# zigduino-micro-2.net
KiCad netlist of a schematic drawn in EAGLE
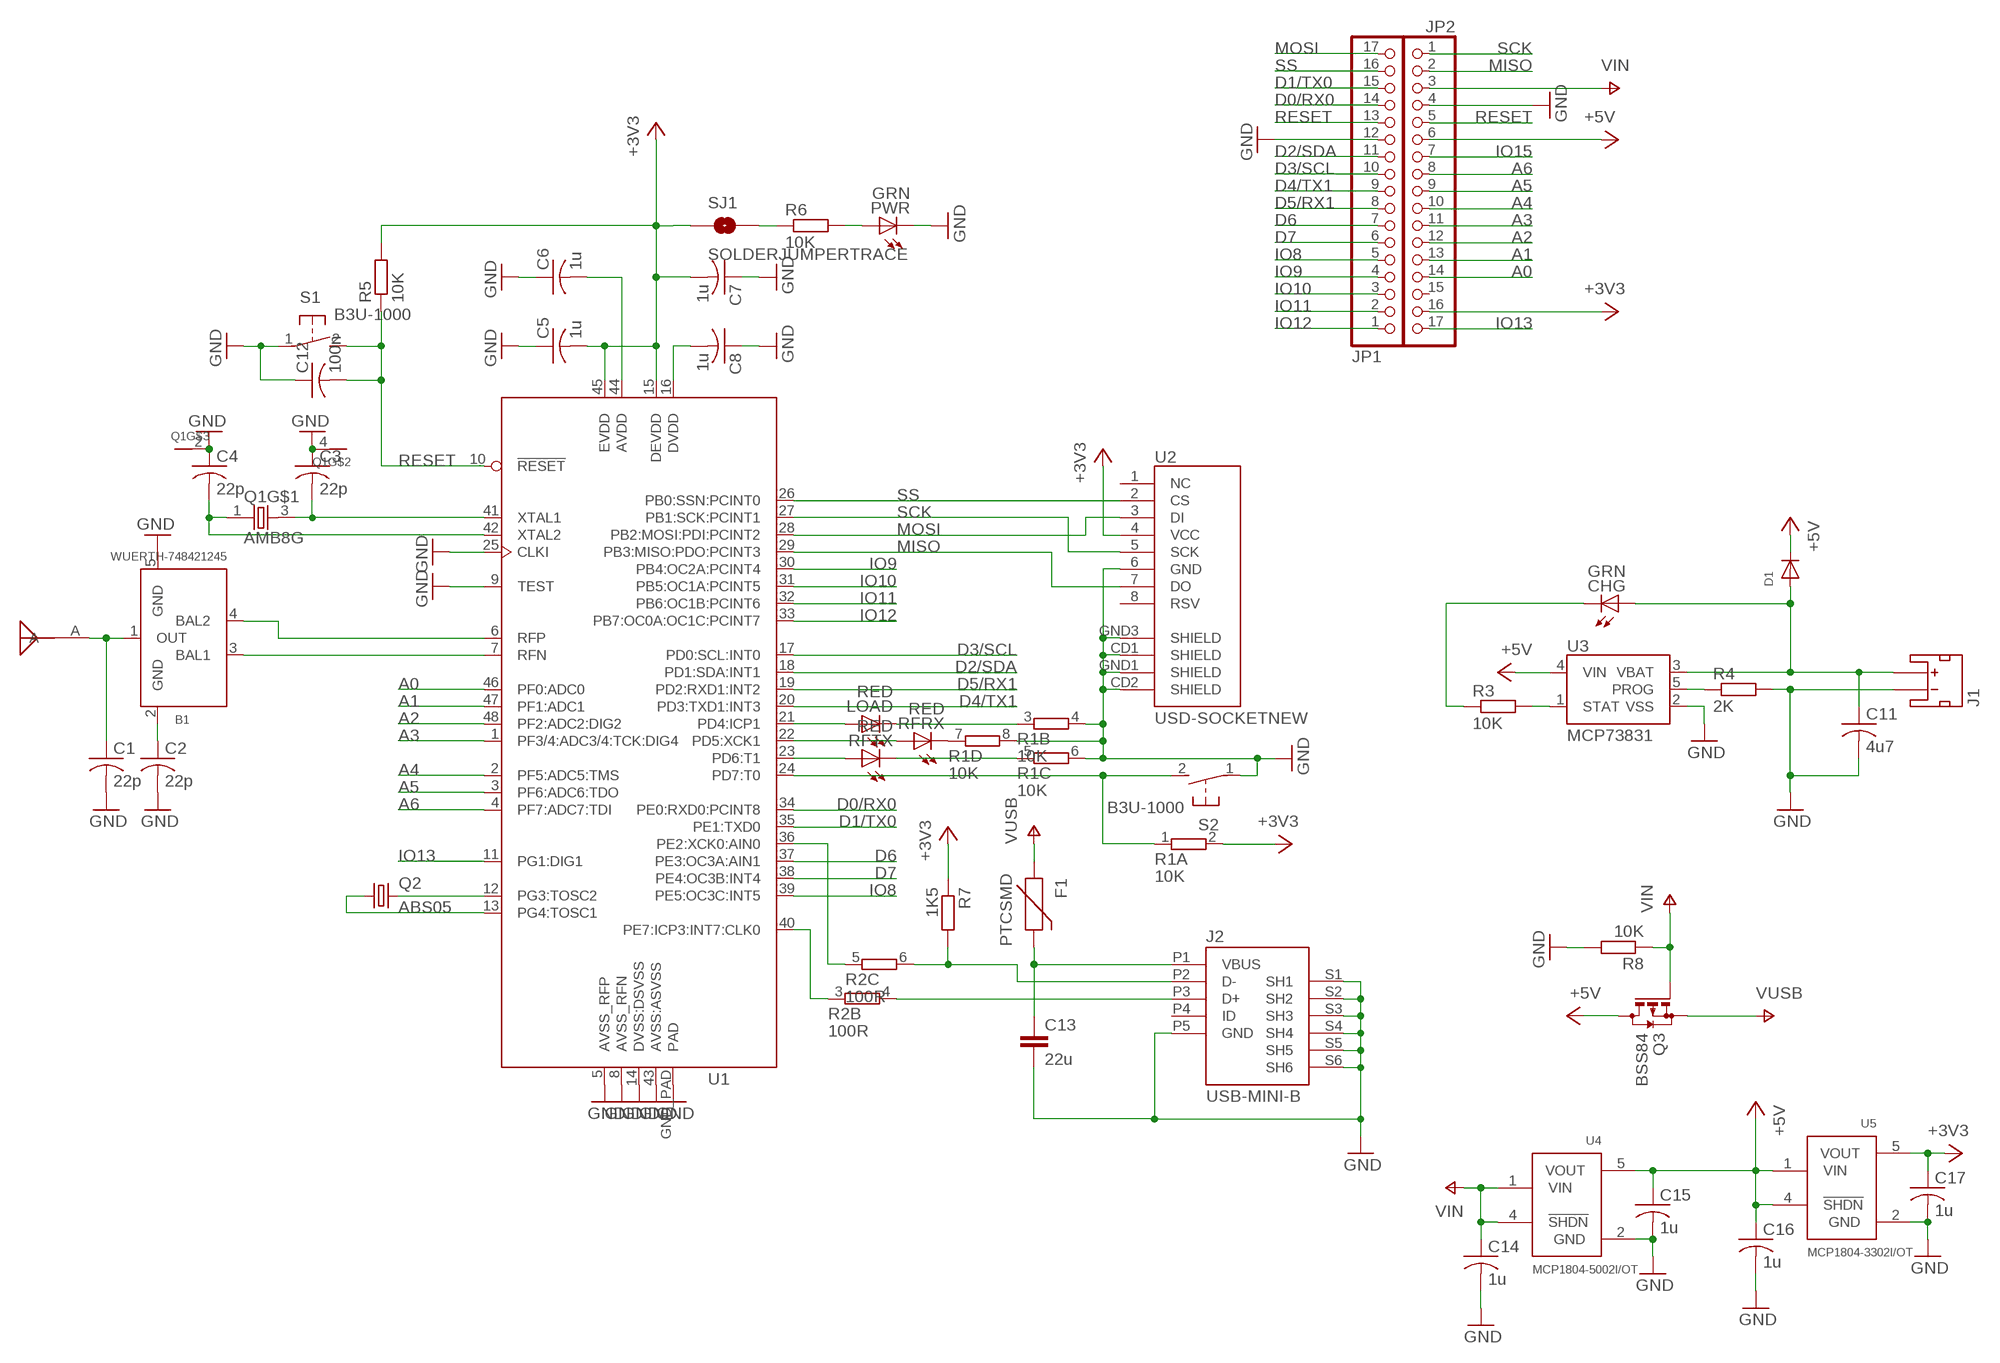
[diagram p0: schematic, sheet 1]

(export (version "E")
  (design (tool "Eeschema 10.0.6"))
  (components
    (comp (ref "ANT1")
      (value "ATMEGA128RFA1_MOLEX-ANT")
      (footprint "eagle-import:ATMEGA128RFA1_MOLEX-ANT")
      (libsource (lib "eagle-import") (part "ATMEGA128RFA1_MOLEX-ANT"))
    )
    (comp (ref "B1")
      (value "WUERTH-748421245")
      (footprint "eagle-import:WURTH-BALUN")
      (libsource (lib "eagle-import") (part "WUERTH-748421245"))
    )
    (comp (ref "C1")
      (value "22p")
      (footprint "eagle-import:C0603")
      (libsource (lib "eagle-import") (part "C-USC0603"))
    )
    (comp (ref "C2")
      (value "22p")
      (footprint "eagle-import:C0603")
      (libsource (lib "eagle-import") (part "C-USC0603"))
    )
    (comp (ref "C3")
      (value "22p")
      (footprint "eagle-import:C0603")
      (libsource (lib "eagle-import") (part "C-USC0603"))
    )
    (comp (ref "C4")
      (value "22p")
      (footprint "eagle-import:C0603")
      (libsource (lib "eagle-import") (part "C-USC0603"))
    )
    (comp (ref "C5")
      (value "1u")
      (footprint "eagle-import:C0603")
      (libsource (lib "eagle-import") (part "C-USC0603"))
    )
    (comp (ref "C6")
      (value "1u")
      (footprint "eagle-import:C0603")
      (libsource (lib "eagle-import") (part "C-USC0603"))
    )
    (comp (ref "C7")
      (value "1u")
      (footprint "eagle-import:C0603")
      (libsource (lib "eagle-import") (part "C-USC0603"))
    )
    (comp (ref "C8")
      (value "1u")
      (footprint "eagle-import:C0603")
      (libsource (lib "eagle-import") (part "C-USC0603"))
    )
    (comp (ref "C11")
      (value "4u7")
      (footprint "eagle-import:C0603")
      (libsource (lib "eagle-import") (part "C-USC0603"))
    )
    (comp (ref "C12")
      (value "100n")
      (footprint "eagle-import:C0603")
      (libsource (lib "eagle-import") (part "C-USC0603"))
    )
    (comp (ref "C13")
      (value "22u")
      (footprint "eagle-import:C0805")
      (libsource (lib "eagle-import") (part "C-EUC0805"))
    )
    (comp (ref "C14")
      (value "1u")
      (footprint "eagle-import:C0603")
      (libsource (lib "eagle-import") (part "C-USC0603"))
    )
    (comp (ref "C15")
      (value "1u")
      (footprint "eagle-import:C0603")
      (libsource (lib "eagle-import") (part "C-USC0603"))
    )
    (comp (ref "C16")
      (value "1u")
      (footprint "eagle-import:C0603")
      (libsource (lib "eagle-import") (part "C-USC0603"))
    )
    (comp (ref "C17")
      (value "1u")
      (footprint "eagle-import:C0603")
      (libsource (lib "eagle-import") (part "C-USC0603"))
    )
    (comp (ref "CHG")
      (value "GRN")
      (footprint "eagle-import:CHIPLED_0603")
      (libsource (lib "eagle-import") (part "LEDCHIPLED_0603"))
    )
    (comp (ref "D1")
      (value "DIODESOD-123")
      (footprint "eagle-import:SOD-123")
      (libsource (lib "eagle-import") (part "DIODESOD-123"))
    )
    (comp (ref "F1")
      (value "PTCSMD")
      (footprint "eagle-import:PTC-1206")
      (libsource (lib "eagle-import") (part "PTCSMD"))
    )
    (comp (ref "J1")
      (value "JST_2MM_MALE")
      (footprint "eagle-import:JST-2-SMD")
      (libsource (lib "eagle-import") (part "JST_2MM_MALE"))
    )
    (comp (ref "J2")
      (value "USB-MINI-B")
      (footprint "eagle-import:SMARTPRJ_CON2_USB_MICRO_B_AT")
      (libsource (lib "eagle-import") (part "USB-MINI-B"))
    )
    (comp (ref "JP1")
      (value "PINHD-1X17_2.54-SMD")
      (footprint "eagle-import:1X17SMD")
      (libsource (lib "eagle-import") (part "PINHD-1X17_2.54-SMD"))
    )
    (comp (ref "JP2")
      (value "PINHD-1X17_2.54-SMD")
      (footprint "eagle-import:1X17SMD")
      (libsource (lib "eagle-import") (part "PINHD-1X17_2.54-SMD"))
    )
    (comp (ref "LOAD")
      (value "RED")
      (footprint "eagle-import:CHIPLED_0603")
      (libsource (lib "eagle-import") (part "LEDCHIPLED_0603"))
    )
    (comp (ref "PWR")
      (value "GRN")
      (footprint "eagle-import:CHIPLED_0603")
      (libsource (lib "eagle-import") (part "LEDCHIPLED_0603"))
    )
    (comp (ref "Q1")
      (value "AMB8G")
      (footprint "eagle-import:ABM8G")
      (libsource (lib "eagle-import") (part "AMB8G"))
    )
    (comp (ref "Q2")
      (value "ABS05")
      (footprint "eagle-import:ABS05")
      (libsource (lib "eagle-import") (part "ABS05"))
    )
    (comp (ref "Q3")
      (value "BSS84")
      (footprint "eagle-import:SOT23")
      (libsource (lib "eagle-import") (part "BSS84"))
    )
    (comp (ref "R1")
      (value "10K")
      (footprint "eagle-import:CTS742C083-RES")
      (libsource (lib "eagle-import") (part "4R-NCTS742C083"))
    )
    (comp (ref "R2")
      (value "100R")
      (footprint "eagle-import:CTS742C083-RES")
      (libsource (lib "eagle-import") (part "4R-NCTS742C083"))
    )
    (comp (ref "R3")
      (value "10K")
      (footprint "eagle-import:R0603")
      (libsource (lib "eagle-import") (part "R-EU_R0603"))
    )
    (comp (ref "R4")
      (value "2K")
      (footprint "eagle-import:R0603")
      (libsource (lib "eagle-import") (part "R-EU_R0603"))
    )
    (comp (ref "R5")
      (value "10K")
      (footprint "eagle-import:R0603")
      (libsource (lib "eagle-import") (part "R-EU_R0603"))
    )
    (comp (ref "R6")
      (value "10K")
      (footprint "eagle-import:R0603")
      (libsource (lib "eagle-import") (part "R-EU_R0603"))
    )
    (comp (ref "R7")
      (value "1K5")
      (footprint "eagle-import:R0603")
      (libsource (lib "eagle-import") (part "R-EU_R0603"))
    )
    (comp (ref "R8")
      (value "10K")
      (footprint "eagle-import:R0603")
      (libsource (lib "eagle-import") (part "R-EU_R0603"))
    )
    (comp (ref "RFRX")
      (value "RED")
      (footprint "eagle-import:CHIPLED_0603")
      (libsource (lib "eagle-import") (part "LEDCHIPLED_0603"))
    )
    (comp (ref "RFTX")
      (value "RED")
      (footprint "eagle-import:CHIPLED_0603")
      (libsource (lib "eagle-import") (part "LEDCHIPLED_0603"))
    )
    (comp (ref "S1")
      (value "B3U-1000")
      (footprint "eagle-import:B3U")
      (libsource (lib "eagle-import") (part "B3U-1000"))
    )
    (comp (ref "S2")
      (value "B3U-1000")
      (footprint "eagle-import:B3U")
      (libsource (lib "eagle-import") (part "B3U-1000"))
    )
    (comp (ref "SJ1")
      (value "SOLDERJUMPERTRACE")
      (footprint "eagle-import:SJ_2S-TRACE")
      (libsource (lib "eagle-import") (part "SOLDERJUMPERTRACE"))
    )
    (comp (ref "U1")
      (value "ATMEGA1284RFR2")
      (footprint "eagle-import:QFN48")
      (libsource (lib "eagle-import") (part "ATMEGA1284RFR2"))
    )
    (comp (ref "U2")
      (value "USD-SOCKETNEW")
      (footprint "eagle-import:MICRO-SD-SOCKET-PP")
      (libsource (lib "eagle-import") (part "USD-SOCKETNEW"))
    )
    (comp (ref "U3")
      (value "MCP73831")
      (footprint "eagle-import:SOT23-5")
      (libsource (lib "eagle-import") (part "MCP73831"))
    )
    (comp (ref "U4")
      (value "MCP1804-5002I/OT")
      (footprint "eagle-import:SOT23-5L")
      (libsource (lib "eagle-import") (part "MCP1804-5002I/OT"))
    )
    (comp (ref "U5")
      (value "MCP1804-3302I/OT")
      (footprint "eagle-import:SOT23-5L")
      (libsource (lib "eagle-import") (part "MCP1804-3302I/OT"))
    )
  )
  (nets
    (net (code "1") (name "+3V3") (class "Default")
      (node (ref "C17") (pin "1") (pinfunction "1_1") (pintype "passive"))
      (node (ref "C5") (pin "2") (pinfunction "2_2") (pintype "passive"))
      (node (ref "C7") (pin "2") (pinfunction "2_2") (pintype "passive"))
      (node (ref "JP2") (pin "16") (pinfunction "16_16") (pintype "passive"))
      (node (ref "R1") (pin "2") (pinfunction "2_2") (pintype "passive"))
      (node (ref "R5") (pin "2") (pinfunction "2_2") (pintype "passive"))
      (node (ref "R7") (pin "1") (pinfunction "1_1") (pintype "passive"))
      (node (ref "SJ1") (pin "1") (pinfunction "1_1") (pintype "passive"))
      (node (ref "U1") (pin "15") (pinfunction "DEVDD_15") (pintype "bidirectional"))
      (node (ref "U1") (pin "45") (pinfunction "EVDD_45") (pintype "bidirectional"))
      (node (ref "U2") (pin "4") (pinfunction "VCC_4") (pintype "bidirectional"))
      (node (ref "U5") (pin "5") (pinfunction "VOUT_5") (pintype "bidirectional"))
    )
    (net (code "2") (name "+5V") (class "Default")
      (node (ref "C15") (pin "1") (pinfunction "1_1") (pintype "passive"))
      (node (ref "C16") (pin "1") (pinfunction "1_1") (pintype "passive"))
      (node (ref "D1") (pin "C") (pinfunction "C_C") (pintype "passive"))
      (node (ref "JP2") (pin "6") (pinfunction "6_6") (pintype "passive"))
      (node (ref "Q3") (pin "3") (pinfunction "D_3") (pintype "passive"))
      (node (ref "U3") (pin "4") (pinfunction "VIN_4") (pintype "power_in"))
      (node (ref "U4") (pin "5") (pinfunction "VOUT_5") (pintype "bidirectional"))
      (node (ref "U5") (pin "1") (pinfunction "VIN_1") (pintype "bidirectional"))
      (node (ref "U5") (pin "4") (pinfunction "~{SHDN}_4") (pintype "bidirectional"))
    )
    (net (code "3") (name "/A0") (class "Default")
      (node (ref "JP2") (pin "14") (pinfunction "14_14") (pintype "passive"))
      (node (ref "U1") (pin "46") (pinfunction "PF0:ADC0_46") (pintype "bidirectional"))
    )
    (net (code "4") (name "/A1") (class "Default")
      (node (ref "JP2") (pin "13") (pinfunction "13_13") (pintype "passive"))
      (node (ref "U1") (pin "47") (pinfunction "PF1:ADC1_47") (pintype "bidirectional"))
    )
    (net (code "5") (name "/A2") (class "Default")
      (node (ref "JP2") (pin "12") (pinfunction "12_12") (pintype "passive"))
      (node (ref "U1") (pin "48") (pinfunction "PF2:ADC2:DIG2_48") (pintype "bidirectional"))
    )
    (net (code "6") (name "/A3") (class "Default")
      (node (ref "JP2") (pin "11") (pinfunction "11_11") (pintype "passive"))
      (node (ref "U1") (pin "1") (pinfunction "PF3/4:ADC3/4:TCK:DIG4_1") (pintype "bidirectional"))
    )
    (net (code "7") (name "/A4") (class "Default")
      (node (ref "JP2") (pin "10") (pinfunction "10_10") (pintype "passive"))
      (node (ref "U1") (pin "2") (pinfunction "PF5:ADC5:TMS_2") (pintype "bidirectional"))
    )
    (net (code "8") (name "/A5") (class "Default")
      (node (ref "JP2") (pin "9") (pinfunction "9_9") (pintype "passive"))
      (node (ref "U1") (pin "3") (pinfunction "PF6:ADC6:TDO_3") (pintype "bidirectional"))
    )
    (net (code "9") (name "/A6") (class "Default")
      (node (ref "JP2") (pin "8") (pinfunction "8_8") (pintype "passive"))
      (node (ref "U1") (pin "4") (pinfunction "PF7:ADC7:TDI_4") (pintype "bidirectional"))
    )
    (net (code "10") (name "/D0{slash}RX0") (class "Default")
      (node (ref "JP1") (pin "14") (pinfunction "14_14") (pintype "passive"))
      (node (ref "U1") (pin "34") (pinfunction "PE0:RXD0:PCINT8_34") (pintype "bidirectional"))
    )
    (net (code "11") (name "/D1{slash}TX0") (class "Default")
      (node (ref "JP1") (pin "15") (pinfunction "15_15") (pintype "passive"))
      (node (ref "U1") (pin "35") (pinfunction "PE1:TXD0_35") (pintype "bidirectional"))
    )
    (net (code "12") (name "/D2{slash}SDA") (class "Default")
      (node (ref "JP1") (pin "11") (pinfunction "11_11") (pintype "passive"))
      (node (ref "U1") (pin "18") (pinfunction "PD1:SDA:INT1_18") (pintype "bidirectional"))
    )
    (net (code "13") (name "/D3{slash}SCL") (class "Default")
      (node (ref "JP1") (pin "10") (pinfunction "10_10") (pintype "passive"))
      (node (ref "U1") (pin "17") (pinfunction "PD0:SCL:INT0_17") (pintype "bidirectional"))
    )
    (net (code "14") (name "/D4{slash}TX1") (class "Default")
      (node (ref "JP1") (pin "9") (pinfunction "9_9") (pintype "passive"))
      (node (ref "U1") (pin "20") (pinfunction "PD3:TXD1:INT3_20") (pintype "bidirectional"))
    )
    (net (code "15") (name "/D5{slash}RX1") (class "Default")
      (node (ref "JP1") (pin "8") (pinfunction "8_8") (pintype "passive"))
      (node (ref "U1") (pin "19") (pinfunction "PD2:RXD1:INT2_19") (pintype "bidirectional"))
    )
    (net (code "16") (name "/D6") (class "Default")
      (node (ref "JP1") (pin "7") (pinfunction "7_7") (pintype "passive"))
      (node (ref "U1") (pin "37") (pinfunction "PE3:OC3A:AIN1_37") (pintype "bidirectional"))
    )
    (net (code "17") (name "/D7") (class "Default")
      (node (ref "JP1") (pin "6") (pinfunction "6_6") (pintype "passive"))
      (node (ref "U1") (pin "38") (pinfunction "PE4:OC3B:INT4_38") (pintype "bidirectional"))
    )
    (net (code "18") (name "/IO8") (class "Default")
      (node (ref "JP1") (pin "5") (pinfunction "5_5") (pintype "passive"))
      (node (ref "U1") (pin "39") (pinfunction "PE5:OC3C:INT5_39") (pintype "bidirectional"))
    )
    (net (code "19") (name "/IO9") (class "Default")
      (node (ref "JP1") (pin "4") (pinfunction "4_4") (pintype "passive"))
      (node (ref "U1") (pin "30") (pinfunction "PB4:OC2A:PCINT4_30") (pintype "bidirectional"))
    )
    (net (code "20") (name "/IO10") (class "Default")
      (node (ref "JP1") (pin "3") (pinfunction "3_3") (pintype "passive"))
      (node (ref "U1") (pin "31") (pinfunction "PB5:OC1A:PCINT5_31") (pintype "bidirectional"))
    )
    (net (code "21") (name "/IO11") (class "Default")
      (node (ref "JP1") (pin "2") (pinfunction "2_2") (pintype "passive"))
      (node (ref "U1") (pin "32") (pinfunction "PB6:OC1B:PCINT6_32") (pintype "bidirectional"))
    )
    (net (code "22") (name "/IO12") (class "Default")
      (node (ref "JP1") (pin "1") (pinfunction "1_1") (pintype "passive"))
      (node (ref "U1") (pin "33") (pinfunction "PB7:OC0A:OC1C:PCINT7_33") (pintype "bidirectional"))
    )
    (net (code "23") (name "/IO13") (class "Default")
      (node (ref "JP2") (pin "17") (pinfunction "17_17") (pintype "passive"))
      (node (ref "U1") (pin "11") (pinfunction "PG1:DIG1_11") (pintype "bidirectional"))
    )
    (net (code "24") (name "/IO15") (class "Default")
      (node (ref "JP2") (pin "7") (pinfunction "7_7") (pintype "passive"))
    )
    (net (code "25") (name "/MISO") (class "Default")
      (node (ref "JP2") (pin "2") (pinfunction "2_2") (pintype "passive"))
      (node (ref "U1") (pin "29") (pinfunction "PB3:MISO:PDO:PCINT3_29") (pintype "bidirectional"))
      (node (ref "U2") (pin "7") (pinfunction "DO_7") (pintype "bidirectional"))
    )
    (net (code "26") (name "/MOSI") (class "Default")
      (node (ref "JP1") (pin "17") (pinfunction "17_17") (pintype "passive"))
      (node (ref "U1") (pin "28") (pinfunction "PB2:MOSI:PDI:PCINT2_28") (pintype "bidirectional"))
      (node (ref "U2") (pin "3") (pinfunction "DI_3") (pintype "bidirectional"))
    )
    (net (code "27") (name "/RESET") (class "Default")
      (node (ref "C12") (pin "2") (pinfunction "2_2") (pintype "passive"))
      (node (ref "JP1") (pin "13") (pinfunction "13_13") (pintype "passive"))
      (node (ref "JP2") (pin "5") (pinfunction "5_5") (pintype "passive"))
      (node (ref "R5") (pin "1") (pinfunction "1_1") (pintype "passive"))
      (node (ref "S1") (pin "2") (pinfunction "2_2") (pintype "passive"))
      (node (ref "U1") (pin "10") (pinfunction "~{RESET}_10") (pintype "bidirectional"))
    )
    (net (code "28") (name "/SCK") (class "Default")
      (node (ref "JP2") (pin "1") (pinfunction "1_1") (pintype "passive"))
      (node (ref "U1") (pin "27") (pinfunction "PB1:SCK:PCINT1_27") (pintype "bidirectional"))
      (node (ref "U2") (pin "5") (pinfunction "SCK_5") (pintype "bidirectional"))
    )
    (net (code "29") (name "/SS") (class "Default")
      (node (ref "JP1") (pin "16") (pinfunction "16_16") (pintype "passive"))
      (node (ref "U1") (pin "26") (pinfunction "PB0:SSN:PCINT0_26") (pintype "bidirectional"))
      (node (ref "U2") (pin "2") (pinfunction "CS_2") (pintype "bidirectional"))
    )
    (net (code "30") (name "GND") (class "Default")
      (node (ref "B1") (pin "5") (pinfunction "GND_5") (pintype "bidirectional"))
      (node (ref "C1") (pin "2") (pinfunction "2_2") (pintype "passive"))
      (node (ref "C11") (pin "2") (pinfunction "2_2") (pintype "passive"))
      (node (ref "C12") (pin "1") (pinfunction "1_1") (pintype "passive"))
      (node (ref "C13") (pin "2") (pinfunction "2_2") (pintype "passive"))
      (node (ref "C14") (pin "2") (pinfunction "2_2") (pintype "passive"))
      (node (ref "C15") (pin "2") (pinfunction "2_2") (pintype "passive"))
      (node (ref "C16") (pin "2") (pinfunction "2_2") (pintype "passive"))
      (node (ref "C17") (pin "2") (pinfunction "2_2") (pintype "passive"))
      (node (ref "C2") (pin "2") (pinfunction "2_2") (pintype "passive"))
      (node (ref "C3") (pin "1") (pinfunction "1_1") (pintype "passive"))
      (node (ref "C4") (pin "1") (pinfunction "1_1") (pintype "passive"))
      (node (ref "C5") (pin "1") (pinfunction "1_1") (pintype "passive"))
      (node (ref "C6") (pin "1") (pinfunction "1_1") (pintype "passive"))
      (node (ref "C7") (pin "1") (pinfunction "1_1") (pintype "passive"))
      (node (ref "C8") (pin "1") (pinfunction "1_1") (pintype "passive"))
      (node (ref "J1") (pin "1") (pinfunction "-_1") (pintype "bidirectional"))
      (node (ref "J2") (pin "P5") (pinfunction "GND_P5") (pintype "passive"))
      (node (ref "J2") (pin "S1") (pinfunction "SH1_S1") (pintype "passive"))
      (node (ref "J2") (pin "S2") (pinfunction "SH2_S2") (pintype "passive"))
      (node (ref "J2") (pin "S3") (pinfunction "SH3_S3") (pintype "passive"))
      (node (ref "J2") (pin "S4") (pinfunction "SH4_S4") (pintype "passive"))
      (node (ref "J2") (pin "S5") (pinfunction "SH5_S5") (pintype "passive"))
      (node (ref "J2") (pin "S6") (pinfunction "SH6_S6") (pintype "passive"))
      (node (ref "JP1") (pin "12") (pinfunction "12_12") (pintype "passive"))
      (node (ref "JP2") (pin "4") (pinfunction "4_4") (pintype "passive"))
      (node (ref "PWR") (pin "C") (pinfunction "C_C") (pintype "passive"))
      (node (ref "Q1") (pin "2") (pinfunction "PIN_2") (pintype "bidirectional"))
      (node (ref "Q1") (pin "4") (pinfunction "PIN_4") (pintype "bidirectional"))
      (node (ref "R1") (pin "4") (pinfunction "2_4") (pintype "passive"))
      (node (ref "R1") (pin "6") (pinfunction "2_6") (pintype "passive"))
      (node (ref "R1") (pin "8") (pinfunction "2_8") (pintype "passive"))
      (node (ref "R4") (pin "2") (pinfunction "2_2") (pintype "passive"))
      (node (ref "R8") (pin "2") (pinfunction "2_2") (pintype "passive"))
      (node (ref "S1") (pin "1") (pinfunction "1_1") (pintype "passive"))
      (node (ref "S2") (pin "1") (pinfunction "1_1") (pintype "passive"))
      (node (ref "U1") (pin "14") (pinfunction "DVSS:DSVSS_14") (pintype "bidirectional"))
      (node (ref "U1") (pin "25") (pinfunction "CLKI_25") (pintype "bidirectional"))
      (node (ref "U1") (pin "43") (pinfunction "AVSS:ASVSS_43") (pintype "bidirectional"))
      (node (ref "U1") (pin "5") (pinfunction "AVSS_RFP_5") (pintype "bidirectional"))
      (node (ref "U1") (pin "8") (pinfunction "AVSS_RFN_8") (pintype "bidirectional"))
      (node (ref "U1") (pin "9") (pinfunction "TEST_9") (pintype "bidirectional"))
      (node (ref "U1") (pin "GND_PAD") (pinfunction "PAD_GND_PAD") (pintype "bidirectional"))
      (node (ref "U2") (pin "6") (pinfunction "GND_6") (pintype "bidirectional"))
      (node (ref "U2") (pin "CD1") (pinfunction "SHIELD_CD1") (pintype "bidirectional"))
      (node (ref "U2") (pin "CD2") (pinfunction "SHIELD_CD2") (pintype "bidirectional"))
      (node (ref "U2") (pin "GND1") (pinfunction "SHIELD_GND1") (pintype "bidirectional"))
      (node (ref "U2") (pin "GND3") (pinfunction "SHIELD_GND3") (pintype "bidirectional"))
      (node (ref "U3") (pin "2") (pinfunction "VSS_2") (pintype "power_in"))
      (node (ref "U4") (pin "2") (pinfunction "GND_2") (pintype "bidirectional"))
      (node (ref "U5") (pin "2") (pinfunction "GND_2") (pintype "bidirectional"))
    )
    (net (code "31") (name "Net-(B1-BAL1)") (class "Default")
      (node (ref "B1") (pin "3") (pinfunction "BAL1_3") (pintype "bidirectional"))
      (node (ref "U1") (pin "7") (pinfunction "RFN_7") (pintype "bidirectional"))
    )
    (net (code "32") (name "Net-(B1-BAL2)") (class "Default")
      (node (ref "B1") (pin "4") (pinfunction "BAL2_4") (pintype "bidirectional"))
      (node (ref "U1") (pin "6") (pinfunction "RFP_6") (pintype "bidirectional"))
    )
    (net (code "33") (name "Net-(B1-GND-Pad2)") (class "Default")
      (node (ref "B1") (pin "2") (pinfunction "GND_2") (pintype "bidirectional"))
      (node (ref "C2") (pin "1") (pinfunction "1_1") (pintype "passive"))
    )
    (net (code "34") (name "Net-(B1-OUT)") (class "Default")
      (node (ref "ANT1") (pin "A") (pinfunction "A_A") (pintype "bidirectional"))
      (node (ref "B1") (pin "1") (pinfunction "OUT_1") (pintype "bidirectional"))
      (node (ref "C1") (pin "1") (pinfunction "1_1") (pintype "passive"))
    )
    (net (code "35") (name "Net-(CHG-PadC)") (class "Default")
      (node (ref "CHG") (pin "C") (pinfunction "C_C") (pintype "passive"))
      (node (ref "R3") (pin "1") (pinfunction "1_1") (pintype "passive"))
    )
    (net (code "36") (name "Net-(J1-+)") (class "Default")
      (node (ref "C11") (pin "1") (pinfunction "1_1") (pintype "passive"))
      (node (ref "CHG") (pin "A") (pinfunction "A_A") (pintype "passive"))
      (node (ref "D1") (pin "A") (pinfunction "A_A") (pintype "passive"))
      (node (ref "J1") (pin "2") (pinfunction "+_2") (pintype "bidirectional"))
      (node (ref "U3") (pin "3") (pinfunction "VBAT_3") (pintype "power_in"))
    )
    (net (code "37") (name "Net-(J2-D+)") (class "Default")
      (node (ref "J2") (pin "P3") (pinfunction "D+_P3") (pintype "bidirectional"))
      (node (ref "R2") (pin "4") (pinfunction "2_4") (pintype "passive"))
    )
    (net (code "38") (name "Net-(J2-D-)") (class "Default")
      (node (ref "J2") (pin "P2") (pinfunction "D-_P2") (pintype "bidirectional"))
      (node (ref "R2") (pin "6") (pinfunction "2_6") (pintype "passive"))
      (node (ref "R7") (pin "2") (pinfunction "2_2") (pintype "passive"))
    )
    (net (code "39") (name "Net-(J2-VBUS)") (class "Default")
      (node (ref "C13") (pin "1") (pinfunction "1_1") (pintype "passive"))
      (node (ref "F1") (pin "2") (pinfunction "2_2") (pintype "bidirectional"))
      (node (ref "J2") (pin "P1") (pinfunction "VBUS_P1") (pintype "power_in"))
    )
    (net (code "40") (name "Net-(PWR-PadA)") (class "Default")
      (node (ref "PWR") (pin "A") (pinfunction "A_A") (pintype "passive"))
      (node (ref "R6") (pin "2") (pinfunction "2_2") (pintype "passive"))
    )
    (net (code "41") (name "Net-(Q1A-2)") (class "Default")
      (node (ref "C3") (pin "2") (pinfunction "2_2") (pintype "passive"))
      (node (ref "Q1") (pin "3") (pinfunction "2_3") (pintype "passive"))
      (node (ref "U1") (pin "41") (pinfunction "XTAL1_41") (pintype "bidirectional"))
    )
    (net (code "42") (name "Net-(R1B-1)") (class "Default")
      (node (ref "LOAD") (pin "C") (pinfunction "C_C") (pintype "passive"))
      (node (ref "R1") (pin "3") (pinfunction "1_3") (pintype "passive"))
    )
    (net (code "43") (name "Net-(R1C-1)") (class "Default")
      (node (ref "R1") (pin "5") (pinfunction "1_5") (pintype "passive"))
      (node (ref "RFTX") (pin "C") (pinfunction "C_C") (pintype "passive"))
    )
    (net (code "44") (name "Net-(R1D-1)") (class "Default")
      (node (ref "R1") (pin "7") (pinfunction "1_7") (pintype "passive"))
      (node (ref "RFRX") (pin "C") (pinfunction "C_C") (pintype "passive"))
    )
    (net (code "45") (name "Net-(R2B-1)") (class "Default")
      (node (ref "R2") (pin "3") (pinfunction "1_3") (pintype "passive"))
      (node (ref "U1") (pin "40") (pinfunction "PE7:ICP3:INT7:CLK0_40") (pintype "bidirectional"))
    )
    (net (code "46") (name "Net-(R2C-1)") (class "Default")
      (node (ref "R2") (pin "5") (pinfunction "1_5") (pintype "passive"))
      (node (ref "U1") (pin "36") (pinfunction "PE2:XCK0:AIN0_36") (pintype "bidirectional"))
    )
    (net (code "47") (name "Net-(R6-Pad1)") (class "Default")
      (node (ref "R6") (pin "1") (pinfunction "1_1") (pintype "passive"))
      (node (ref "SJ1") (pin "2") (pinfunction "2_2") (pintype "passive"))
    )
    (net (code "48") (name "Net-(U1-AVDD)") (class "Default")
      (node (ref "C6") (pin "2") (pinfunction "2_2") (pintype "passive"))
      (node (ref "U1") (pin "44") (pinfunction "AVDD_44") (pintype "bidirectional"))
    )
    (net (code "49") (name "Net-(U1-DVDD)") (class "Default")
      (node (ref "C8") (pin "2") (pinfunction "2_2") (pintype "passive"))
      (node (ref "U1") (pin "16") (pinfunction "DVDD_16") (pintype "bidirectional"))
    )
    (net (code "50") (name "Net-(U1-PD4:ICP1)") (class "Default")
      (node (ref "LOAD") (pin "A") (pinfunction "A_A") (pintype "passive"))
      (node (ref "U1") (pin "21") (pinfunction "PD4:ICP1_21") (pintype "bidirectional"))
    )
    (net (code "51") (name "Net-(U1-PD5:XCK1)") (class "Default")
      (node (ref "RFRX") (pin "A") (pinfunction "A_A") (pintype "passive"))
      (node (ref "U1") (pin "22") (pinfunction "PD5:XCK1_22") (pintype "bidirectional"))
    )
    (net (code "52") (name "Net-(U1-PD6:T1)") (class "Default")
      (node (ref "RFTX") (pin "A") (pinfunction "A_A") (pintype "passive"))
      (node (ref "U1") (pin "23") (pinfunction "PD6:T1_23") (pintype "bidirectional"))
    )
    (net (code "53") (name "Net-(U1-PD7:T0)") (class "Default")
      (node (ref "R1") (pin "1") (pinfunction "1_1") (pintype "passive"))
      (node (ref "S2") (pin "2") (pinfunction "2_2") (pintype "passive"))
      (node (ref "U1") (pin "24") (pinfunction "PD7:T0_24") (pintype "bidirectional"))
    )
    (net (code "54") (name "Net-(U1-PG3:TOSC2)") (class "Default")
      (node (ref "Q2") (pin "2") (pinfunction "2_2") (pintype "passive"))
      (node (ref "U1") (pin "12") (pinfunction "PG3:TOSC2_12") (pintype "bidirectional"))
    )
    (net (code "55") (name "Net-(U1-PG4:TOSC1)") (class "Default")
      (node (ref "Q2") (pin "1") (pinfunction "1_1") (pintype "passive"))
      (node (ref "U1") (pin "13") (pinfunction "PG4:TOSC1_13") (pintype "bidirectional"))
    )
    (net (code "56") (name "Net-(U1-XTAL2)") (class "Default")
      (node (ref "C4") (pin "2") (pinfunction "2_2") (pintype "passive"))
      (node (ref "Q1") (pin "1") (pinfunction "1_1") (pintype "passive"))
      (node (ref "U1") (pin "42") (pinfunction "XTAL2_42") (pintype "bidirectional"))
    )
    (net (code "57") (name "Net-(U3-PROG)") (class "Default")
      (node (ref "R4") (pin "1") (pinfunction "1_1") (pintype "passive"))
      (node (ref "U3") (pin "5") (pinfunction "PROG_5") (pintype "input"))
    )
    (net (code "58") (name "Net-(U3-STAT)") (class "Default")
      (node (ref "R3") (pin "2") (pinfunction "2_2") (pintype "passive"))
      (node (ref "U3") (pin "1") (pinfunction "STAT_1") (pintype "output"))
    )
    (net (code "59") (name "VIN") (class "Default")
      (node (ref "C14") (pin "1") (pinfunction "1_1") (pintype "passive"))
      (node (ref "JP2") (pin "3") (pinfunction "3_3") (pintype "passive"))
      (node (ref "Q3") (pin "1") (pinfunction "G_1") (pintype "passive"))
      (node (ref "R8") (pin "1") (pinfunction "1_1") (pintype "passive"))
      (node (ref "U4") (pin "1") (pinfunction "VIN_1") (pintype "bidirectional"))
      (node (ref "U4") (pin "4") (pinfunction "~{SHDN}_4") (pintype "bidirectional"))
    )
    (net (code "60") (name "VUSB") (class "Default")
      (node (ref "F1") (pin "1") (pinfunction "1_1") (pintype "bidirectional"))
      (node (ref "Q3") (pin "2") (pinfunction "S_2") (pintype "passive"))
    )
    (net (code "61") (name "unconnected-(J1-PAD1-PadNC1)") (class "Default")
      (node (ref "J1") (pin "NC1") (pinfunction "PAD1_NC1") (pintype "bidirectional"))
    )
    (net (code "62") (name "unconnected-(J1-PAD2-PadNC2)") (class "Default")
      (node (ref "J1") (pin "NC2") (pinfunction "PAD2_NC2") (pintype "bidirectional"))
    )
    (net (code "63") (name "unconnected-(J2-ID-PadP4)") (class "Default")
      (node (ref "J2") (pin "P4") (pinfunction "ID_P4") (pintype "bidirectional"))
    )
    (net (code "64") (name "unconnected-(JP2-Pad15)") (class "Default")
      (node (ref "JP2") (pin "15") (pinfunction "15_15") (pintype "passive"))
    )
    (net (code "65") (name "unconnected-(U2-NC-Pad1)") (class "Default")
      (node (ref "U2") (pin "1") (pinfunction "NC_1") (pintype "bidirectional"))
    )
    (net (code "66") (name "unconnected-(U2-RSV-Pad8)") (class "Default")
      (node (ref "U2") (pin "8") (pinfunction "RSV_8") (pintype "bidirectional"))
    )
  )
)
